# MP2307.net
KiCad netlist of a schematic drawn in Altium Designer
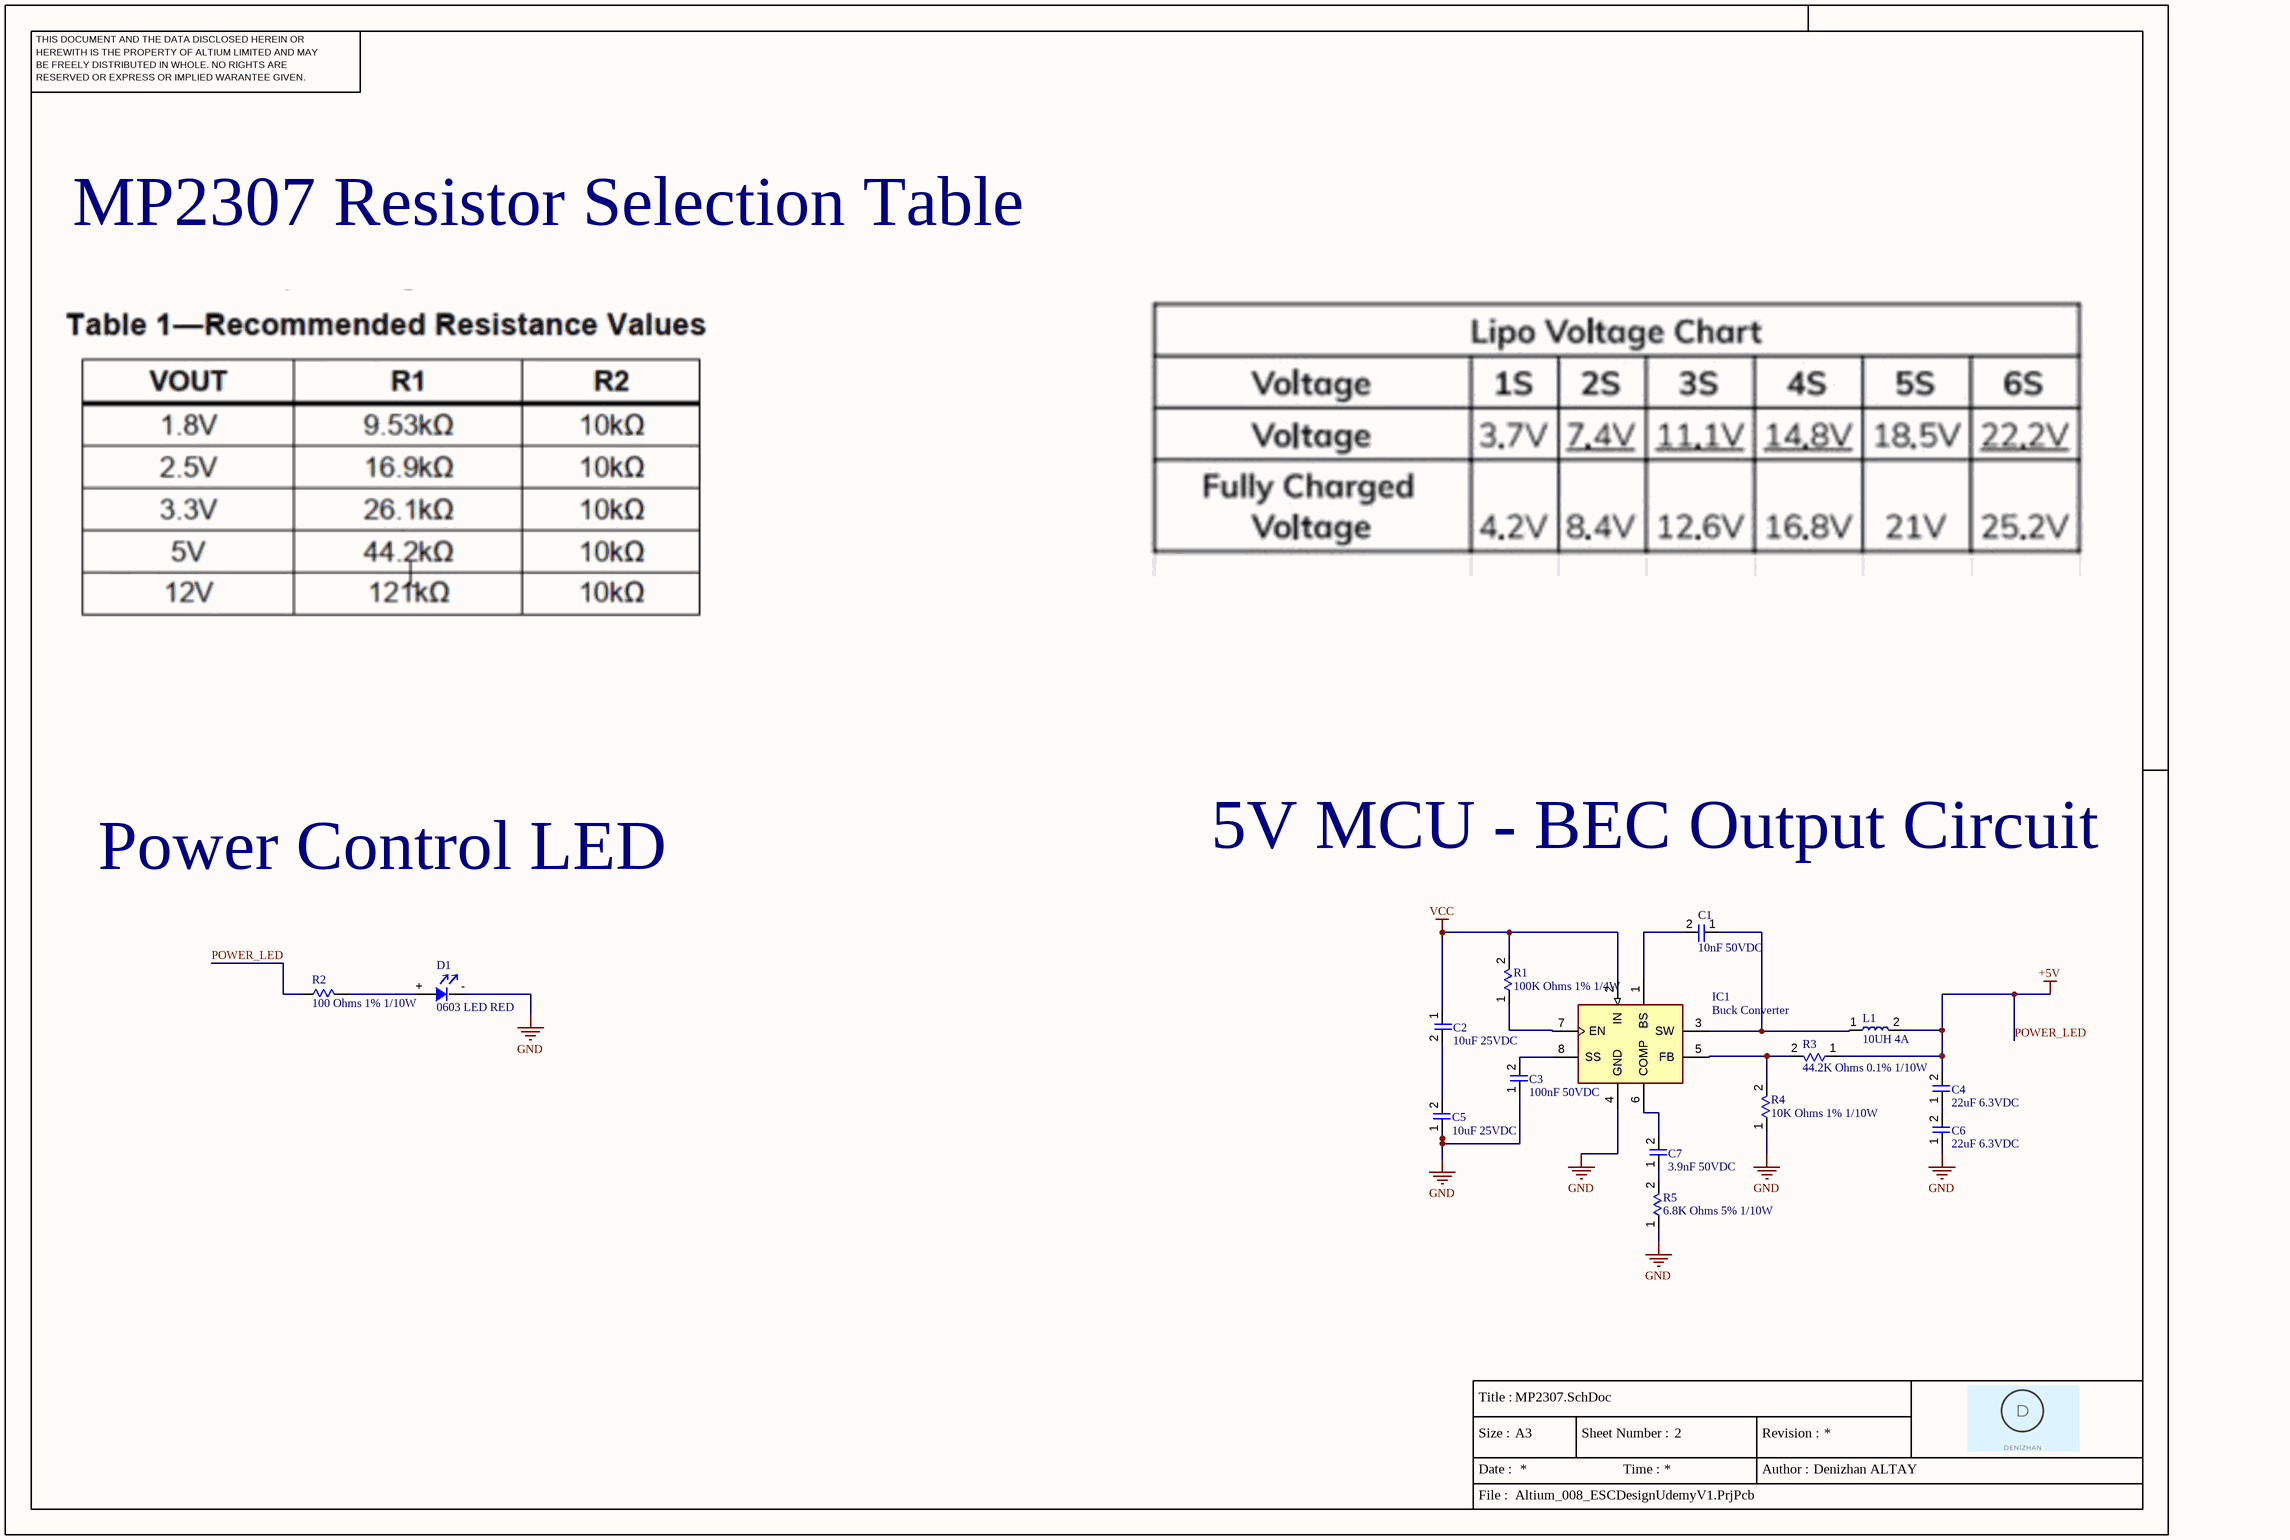
[diagram p0: MP2307.SchDoc]

(export (version "E")
  (design (tool "Eeschema 10.0.6"))
  (components
    (comp (ref "C1")
      (value "10nF 50VDC")
      (footprint "0603_UnP_Capacitor")
      (description "CL10B103KB8NNNC - MLCC (1608) 0603 10nF 50VDC ±10% X7R")
      (fields (field (name "MANUFACTURER") "SAMSUNG") (field (name "PART NUMBER") "CL10B103KB8NNNC"))
      (libsource (lib "GeneralDASchematicsLib") (part "CL10B103KB8NNNC - MLCC (1608) 0603 10nF 50VDC ±10% X7R"))
    )
    (comp (ref "C2")
      (value "10uF 25VDC")
      (footprint "0603_UnP_Capacitor")
      (description "MCF03MTX250106 - MLCC (1608) 0603 10uF 25VDC ±20% X5R")
      (fields (field (name "MANUFACTURER") "VIKING") (field (name "PART NUMBER") "MCF03MTX250106"))
      (libsource (lib "GeneralDASchematicsLib") (part "MCF03MTX250106 - MLCC 0603 10uF 25VDC ±20% X5R"))
    )
    (comp (ref "C3")
      (value "100nF 50VDC")
      (footprint "0603_UnP_Capacitor")
      (description "MCF03KTB500104 - MLCC (1608) 0603 100nF 50VDC ±10% X7R")
      (fields (field (name "MANUFACTURER") "VIKING") (field (name "PART NUMBER") "MCF03MTX250106"))
      (libsource (lib "GeneralDASchematicsLib") (part "MCF03KTB500104 - MLCC 0603 100nF 50VDC ±10% X7R"))
    )
    (comp (ref "C4")
      (value "22uF 6.3VDC")
      (footprint "0603_UnP_Capacitor")
      (description "CL10A226MQ8NRNC - MLCC (1608) 0603 22uF 6.3VDC ±20% X5R")
      (fields (field (name "MANUFACTURER") "SAMSUNG") (field (name "PART NUMBER") "CL10B103KB8NNNC"))
      (libsource (lib "GeneralDASchematicsLib") (part "CL10A226MQ8NRNC - MLCC (1608) 0603 22uF 6.3VDC ±20% X5R"))
    )
    (comp (ref "C5")
      (value "10uF 25VDC")
      (footprint "0603_UnP_Capacitor")
      (description "MCF03MTX250106 - MLCC (1608) 0603 10uF 25VDC ±20% X5R")
      (fields (field (name "MANUFACTURER") "VIKING") (field (name "PART NUMBER") "MCF03MTX250106"))
      (libsource (lib "GeneralDASchematicsLib") (part "MCF03MTX250106 - MLCC 0603 10uF 25VDC ±20% X5R"))
    )
    (comp (ref "C6")
      (value "22uF 6.3VDC")
      (footprint "0603_UnP_Capacitor")
      (description "CL10A226MQ8NRNC - MLCC (1608) 0603 22uF 6.3VDC ±20% X5R")
      (fields (field (name "MANUFACTURER") "SAMSUNG") (field (name "PART NUMBER") "CL10B103KB8NNNC"))
      (libsource (lib "GeneralDASchematicsLib") (part "CL10A226MQ8NRNC - MLCC (1608) 0603 22uF 6.3VDC ±20% X5R"))
    )
    (comp (ref "C7")
      (value "3.9nF 50VDC")
      (footprint "0603_UnP_Capacitor")
      (description "CL10B392KB8NNNC - MLCC (1608) 0603 3.9nF 50VDC ±10% X7R")
      (fields (field (name "MANUFACTURER") "SAMSUNG") (field (name "PART NUMBER") "CL10B103KB8NNNC"))
      (libsource (lib "GeneralDASchematicsLib") (part "CL10B392KB8NNNC - MLCC (1608) 0603 3.9nF 50VDC ±10% X7R"))
    )
    (comp (ref "D1")
      (value "0603 LED RED")
      (footprint "LED Diode 0603")
      (libsource (lib "GeneralDASchematicsLib") (part "0603 LED RED"))
    )
    (comp (ref "IC1")
      (value "Buck Converter")
      (footprint "MP2307_SOIC127P600X170_HS-9N")
      (description "3A and 4.75V-23V voltage regulator.")
      (libsource (lib "GeneralDASchematicsLib") (part "MP2307"))
    )
    (comp (ref "L1")
      (value "10UH 4A")
      (footprint "IHLP-2525CZ-11_Inductor")
      (description "IHLP2525CZER100M11 - INDUCTOR FIXED 10UH 4A 71.2MOHM SMD")
      (libsource (lib "GeneralDASchematicsLib") (part "IHLP2525CZER100M11 - INDUCTOR FIXED 10UH 4A 71.2MOHM SMD"))
    )
    (comp (ref "R1")
      (value "100K Ohms 1% 1/4W")
      (footprint "0603_Resistor_Case")
      (description "RES.(1608) 0603 100K Ohms 1% 1/4W AUTOMOTIV PS03W4F1003T5E")
      (fields (field (name "MANUFACTURER") "ROYALOHM") (field (name "PART NUMBER") "PS03W4F1003T5E"))
      (libsource (lib "GeneralDASchematicsLib") (part "PS03W4F1003T5E - 0603 100K Ohms 1% 1/4W AUTOMOTIV"))
    )
    (comp (ref "R2")
      (value "100 Ohms 1% 1/10W")
      (footprint "0603_Resistor_Case")
      (description "CQ03SAF1000T5E - 0603 100 Ohms 1% 1/10W AUTOMOTIV")
      (fields (field (name "MANUFACTURER") "ROYALOHM") (field (name "PART NUMBER") "CQ03SAF1000T5E"))
      (libsource (lib "GeneralDASchematicsLib") (part "CQ03SAF1000T5E - 0603 100 Ohms 1% 1/10W AUTOMOTIV"))
    )
    (comp (ref "R3")
      (value "44.2K Ohms 0.1% 1/10W")
      (footprint "0603_Resistor_Case")
      (description "TC0325B4422T5F - RES.(1608) 0603 44.2K Ohms 0.1% 1/10W 25PPM")
      (fields (field (name "MANUFACTURER") "ROYALOHM") (field (name "PART NUMBER") "RI0603L104JT"))
      (libsource (lib "GeneralDASchematicsLib") (part "TC0325B4422T5F - 0603 44.2K Ohms 0.1% 1/10W 25PPM"))
    )
    (comp (ref "R4")
      (value "10K Ohms 1% 1/10W")
      (footprint "0603_Resistor_Case")
      (description "RC0603FR-0710KL - 0603 10K Ohms 1% 1/10W 100PPM")
      (fields (field (name "MANUFACTURER") "HOTTECH") (field (name "PART NUMBER") "PS03W4F1003T5E"))
      (libsource (lib "GeneralDASchematicsLib") (part "RC0603FR-0710KL - 0603 10K Ohms 1% 1/10W 100PPM"))
    )
    (comp (ref "R5")
      (value "6.8K Ohms 5% 1/10W")
      (footprint "0603_Resistor_Case")
      (description "RC0603JR-076K8L - 0603 6.8K Ohms 5% 1/10W 100PPM")
      (fields (field (name "MANUFACTURER") "YAGEO") (field (name "PART NUMBER") "RC0603JR-076K8L"))
      (libsource (lib "GeneralDASchematicsLib") (part "RC0603JR-076K8L - 0603 6.8K Ohms 5% 1/10W 100PPM"))
    )
  )
  (nets
    (net (code "1") (name "+5V") (class "Default")
      (node (ref "C4") (pin "2") (pintype "passive"))
      (node (ref "L1") (pin "2") (pintype "passive"))
      (node (ref "R2") (pin "1") (pintype "passive"))
      (node (ref "R3") (pin "1") (pintype "passive"))
    )
    (net (code "2") (name "GND") (class "Default")
      (node (ref "C3") (pin "1") (pintype "passive"))
      (node (ref "C5") (pin "1") (pintype "passive"))
      (node (ref "C6") (pin "1") (pintype "passive"))
      (node (ref "D1") (pin "-") (pintype "passive"))
      (node (ref "IC1") (pin "4") (pinfunction "GND_4") (pintype "power_in"))
      (node (ref "R4") (pin "1") (pintype "passive"))
      (node (ref "R5") (pin "1") (pintype "passive"))
    )
    (net (code "3") (name "Net-(C2-Pad2)") (class "Default")
      (node (ref "C2") (pin "2") (pintype "passive"))
      (node (ref "C5") (pin "2") (pintype "passive"))
    )
    (net (code "4") (name "Net-(C4-Pad1)") (class "Default")
      (node (ref "C4") (pin "1") (pintype "passive"))
      (node (ref "C6") (pin "2") (pintype "passive"))
    )
    (net (code "5") (name "Net-(C7-Pad1)") (class "Default")
      (node (ref "C7") (pin "1") (pintype "passive"))
      (node (ref "R5") (pin "2") (pintype "passive"))
    )
    (net (code "6") (name "Net-(D1-Pad+)") (class "Default")
      (node (ref "D1") (pin "+") (pintype "passive"))
      (node (ref "R2") (pin "2") (pintype "passive"))
    )
    (net (code "7") (name "Net-(IC1-BS)") (class "Default")
      (node (ref "C1") (pin "2") (pintype "passive"))
      (node (ref "IC1") (pin "1") (pinfunction "BS_1") (pintype "power_in"))
    )
    (net (code "8") (name "Net-(IC1-COMP)") (class "Default")
      (node (ref "C7") (pin "2") (pintype "passive"))
      (node (ref "IC1") (pin "6") (pinfunction "COMP_6") (pintype "power_in"))
    )
    (net (code "9") (name "Net-(IC1-EN)") (class "Default")
      (node (ref "IC1") (pin "7") (pinfunction "EN_7") (pintype "power_in"))
      (node (ref "R1") (pin "1") (pintype "passive"))
    )
    (net (code "10") (name "Net-(IC1-FB)") (class "Default")
      (node (ref "IC1") (pin "5") (pinfunction "FB_5") (pintype "power_in"))
      (node (ref "R3") (pin "2") (pintype "passive"))
      (node (ref "R4") (pin "2") (pintype "passive"))
    )
    (net (code "11") (name "Net-(IC1-SS)") (class "Default")
      (node (ref "C3") (pin "2") (pintype "passive"))
      (node (ref "IC1") (pin "8") (pinfunction "SS_8") (pintype "power_in"))
    )
    (net (code "12") (name "Net-(IC1-SW)") (class "Default")
      (node (ref "C1") (pin "1") (pintype "passive"))
      (node (ref "IC1") (pin "3") (pinfunction "SW_3") (pintype "power_in"))
      (node (ref "L1") (pin "1") (pintype "passive"))
    )
    (net (code "13") (name "VCC") (class "Default")
      (node (ref "C2") (pin "1") (pintype "passive"))
      (node (ref "IC1") (pin "2") (pinfunction "IN_2") (pintype "input"))
      (node (ref "R1") (pin "2") (pintype "passive"))
    )
  )
)
